# Zio_Qwiic_Level_Translator_PCA9306.net
KiCad netlist of a schematic drawn in EAGLE
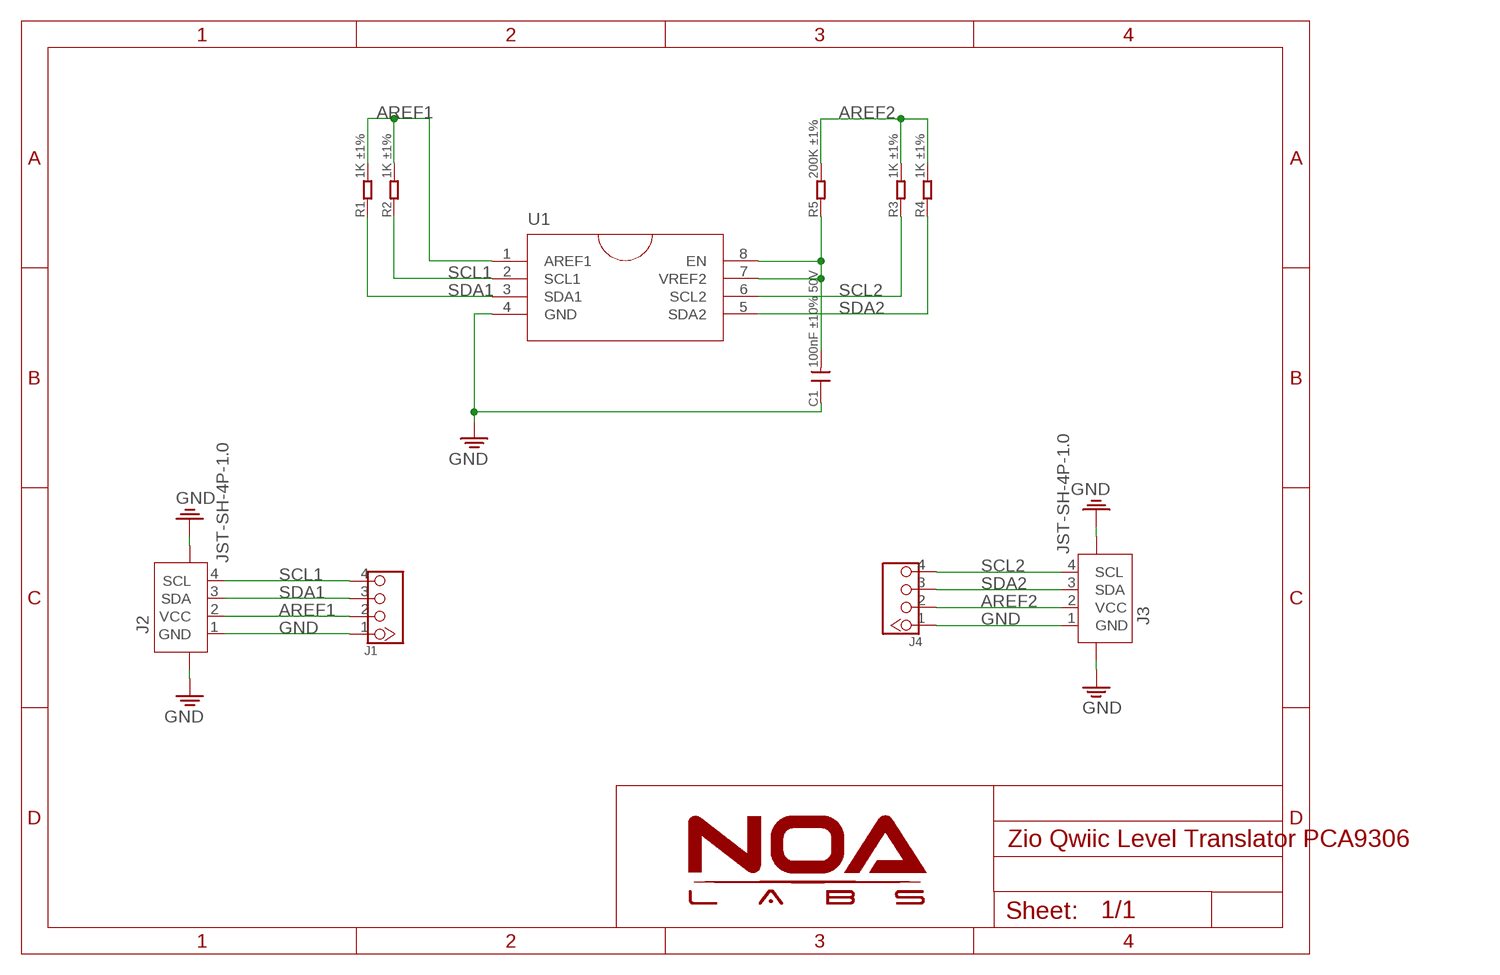
[diagram p0: schematic, sheet 1]

(export (version "E")
  (design (tool "Eeschema 10.0.6"))
  (components
    (comp (ref "C1")
      (value "100nF ±10% 50V")
      (footprint "eagle-import:C0603")
      (libsource (lib "eagle-import") (part "C-0603"))
    )
    (comp (ref "J1")
      (value "HEADER-4P-60/35MIL")
      (footprint "eagle-import:4P-65_35MIL")
      (libsource (lib "eagle-import") (part "HEADER-4P-60/35MIL"))
    )
    (comp (ref "J2")
      (value "JST-SH-4P-1.0")
      (footprint "eagle-import:JST-SH-4P")
      (libsource (lib "eagle-import") (part "JST-SH-4P-1.0"))
    )
    (comp (ref "J3")
      (value "JST-SH-4P-1.0")
      (footprint "eagle-import:JST-SH-4P")
      (libsource (lib "eagle-import") (part "JST-SH-4P-1.0"))
    )
    (comp (ref "J4")
      (value "HEADER-4P-60/35MIL")
      (footprint "eagle-import:4P-65_35MIL")
      (libsource (lib "eagle-import") (part "HEADER-4P-60/35MIL"))
    )
    (comp (ref "R1")
      (value "1K ±1%")
      (footprint "eagle-import:R0603")
      (libsource (lib "eagle-import") (part "R-0603"))
    )
    (comp (ref "R2")
      (value "1K ±1%")
      (footprint "eagle-import:R0603")
      (libsource (lib "eagle-import") (part "R-0603"))
    )
    (comp (ref "R3")
      (value "1K ±1%")
      (footprint "eagle-import:R0603")
      (libsource (lib "eagle-import") (part "R-0603"))
    )
    (comp (ref "R4")
      (value "1K ±1%")
      (footprint "eagle-import:R0603")
      (libsource (lib "eagle-import") (part "R-0603"))
    )
    (comp (ref "R5")
      (value "200K ±1%")
      (footprint "eagle-import:R0603")
      (libsource (lib "eagle-import") (part "R-0603"))
    )
    (comp (ref "U1")
      (value "PCA9306DC")
      (footprint "eagle-import:VSSOP-8")
      (libsource (lib "eagle-import") (part "PCA9306DC"))
    )
  )
  (nets
    (net (code "1") (name "/AREF1") (class "Default")
      (node (ref "J1") (pin "2") (pinfunction "P$2_2") (pintype "bidirectional"))
      (node (ref "J2") (pin "2") (pinfunction "VCC_2") (pintype "bidirectional"))
      (node (ref "R1") (pin "2") (pinfunction "2_2") (pintype "passive"))
      (node (ref "R2") (pin "2") (pinfunction "2_2") (pintype "passive"))
      (node (ref "U1") (pin "1") (pinfunction "AREF1_1") (pintype "bidirectional"))
    )
    (net (code "2") (name "/AREF2") (class "Default")
      (node (ref "J3") (pin "2") (pinfunction "VCC_2") (pintype "bidirectional"))
      (node (ref "J4") (pin "2") (pinfunction "P$2_2") (pintype "bidirectional"))
      (node (ref "R3") (pin "2") (pinfunction "2_2") (pintype "passive"))
      (node (ref "R4") (pin "2") (pinfunction "2_2") (pintype "passive"))
      (node (ref "R5") (pin "2") (pinfunction "2_2") (pintype "passive"))
    )
    (net (code "3") (name "/SCL1") (class "Default")
      (node (ref "J1") (pin "4") (pinfunction "P$4_4") (pintype "bidirectional"))
      (node (ref "J2") (pin "4") (pinfunction "SCL_4") (pintype "bidirectional"))
      (node (ref "R2") (pin "1") (pinfunction "1_1") (pintype "passive"))
      (node (ref "U1") (pin "2") (pinfunction "SCL1_2") (pintype "bidirectional"))
    )
    (net (code "4") (name "/SCL2") (class "Default")
      (node (ref "J3") (pin "4") (pinfunction "SCL_4") (pintype "bidirectional"))
      (node (ref "J4") (pin "4") (pinfunction "P$4_4") (pintype "bidirectional"))
      (node (ref "R3") (pin "1") (pinfunction "1_1") (pintype "passive"))
      (node (ref "U1") (pin "6") (pinfunction "SCL2_6") (pintype "bidirectional"))
    )
    (net (code "5") (name "/SDA1") (class "Default")
      (node (ref "J1") (pin "3") (pinfunction "P$3_3") (pintype "bidirectional"))
      (node (ref "J2") (pin "3") (pinfunction "SDA_3") (pintype "bidirectional"))
      (node (ref "R1") (pin "1") (pinfunction "1_1") (pintype "passive"))
      (node (ref "U1") (pin "3") (pinfunction "SDA1_3") (pintype "bidirectional"))
    )
    (net (code "6") (name "/SDA2") (class "Default")
      (node (ref "J3") (pin "3") (pinfunction "SDA_3") (pintype "bidirectional"))
      (node (ref "J4") (pin "3") (pinfunction "P$3_3") (pintype "bidirectional"))
      (node (ref "R4") (pin "1") (pinfunction "1_1") (pintype "passive"))
      (node (ref "U1") (pin "5") (pinfunction "SDA2_5") (pintype "bidirectional"))
    )
    (net (code "7") (name "GND") (class "Default")
      (node (ref "C1") (pin "1") (pinfunction "1_1") (pintype "passive"))
      (node (ref "J1") (pin "1") (pinfunction "P$1_1") (pintype "bidirectional"))
      (node (ref "J2") (pin "1") (pinfunction "GND_1") (pintype "bidirectional"))
      (node (ref "J2") (pin "NC1") (pinfunction "5_NC1") (pintype "bidirectional"))
      (node (ref "J2") (pin "NC2") (pinfunction "6_NC2") (pintype "bidirectional"))
      (node (ref "J3") (pin "1") (pinfunction "GND_1") (pintype "bidirectional"))
      (node (ref "J3") (pin "NC1") (pinfunction "5_NC1") (pintype "bidirectional"))
      (node (ref "J3") (pin "NC2") (pinfunction "6_NC2") (pintype "bidirectional"))
      (node (ref "J4") (pin "1") (pinfunction "P$1_1") (pintype "bidirectional"))
      (node (ref "U1") (pin "4") (pinfunction "GND_4") (pintype "bidirectional"))
    )
    (net (code "8") (name "Net-(U1-EN)") (class "Default")
      (node (ref "C1") (pin "2") (pinfunction "2_2") (pintype "passive"))
      (node (ref "R5") (pin "1") (pinfunction "1_1") (pintype "passive"))
      (node (ref "U1") (pin "7") (pinfunction "VREF2_7") (pintype "bidirectional"))
      (node (ref "U1") (pin "8") (pinfunction "EN_8") (pintype "bidirectional"))
    )
  )
)
